# Sheet3.net
KiCad netlist of a schematic drawn in Altium Designer
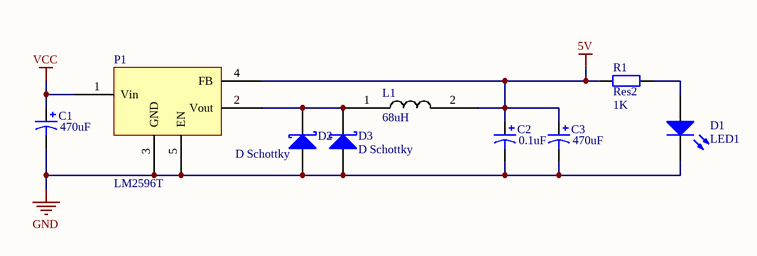
[diagram p0: Sheet3.SchDoc]

(export (version "E")
  (design (tool "Eeschema 10.0.6"))
  (components
    (comp (ref "C1")
      (value "470uF")
      (footprint "C_470uF")
      (description "Polarized Capacitor (Radial)")
      (fields (field (name "Comment") "Cap Pol1") (field (name "PUBLISHER") "Altium Limited"))
      (libsource (lib "Miscellaneous Devices") (part "Cap Pol1"))
    )
    (comp (ref "C2")
      (value "0.1uF")
      (footprint "C-pF")
      (description "Polarized Capacitor (Radial)")
      (fields (field (name "Comment") "Cap Pol1") (field (name "PUBLISHER") "Altium Limited"))
      (libsource (lib "Miscellaneous Devices") (part "Cap Pol1"))
    )
    (comp (ref "C3")
      (value "470uF")
      (footprint "C_470uF")
      (description "Polarized Capacitor (Radial)")
      (fields (field (name "Comment") "Cap Pol1") (field (name "PUBLISHER") "Altium Limited"))
      (libsource (lib "Miscellaneous Devices") (part "Cap Pol1"))
    )
    (comp (ref "D1")
      (value "LED1")
      (footprint "LED")
      (description "Typical RED GaAs LED")
      (fields (field (name "PUBLISHER") "Altium Limited"))
      (libsource (lib "Miscellaneous Devices") (part "LED1"))
    )
    (comp (ref "D2")
      (value "D Schottky")
      (footprint "Diode")
      (description "Schottky Diode")
      (fields (field (name "PUBLISHER") "Altium Limited"))
      (libsource (lib "Miscellaneous Devices") (part "D Schottky"))
    )
    (comp (ref "D3")
      (value "D Schottky")
      (footprint "Diode")
      (description "Schottky Diode")
      (fields (field (name "PUBLISHER") "Altium Limited"))
      (libsource (lib "Miscellaneous Devices") (part "D Schottky"))
    )
    (comp (ref "L1") (value "68uH") (footprint "L-") (libsource (lib "sharing_Library1") (part "L")))
    (comp (ref "P1")
      (value "LM2596T")
      (footprint "LM2596-ChaJian")
      (libsource (lib "sharing_Library1") (part "LM2596T"))
    )
    (comp (ref "R1")
      (value "Res2")
      (footprint "R")
      (description "Resistor")
      (fields (field (name "ALTIUM_VALUE") "1K") (field (name "PUBLISHER") "Altium Limited"))
      (libsource (lib "Miscellaneous Devices") (part "Res2"))
    )
  )
  (nets
    (net (code "1") (name "5V") (class "Default")
      (node (ref "C2") (pin "1") (pinfunction "1_1") (pintype "passive"))
      (node (ref "C3") (pin "1") (pinfunction "1_1") (pintype "passive"))
      (node (ref "L1") (pin "2") (pinfunction "2_2") (pintype "passive"))
      (node (ref "P1") (pin "4") (pinfunction "FB_4") (pintype "passive"))
      (node (ref "R1") (pin "2") (pinfunction "2_2") (pintype "passive"))
    )
    (net (code "2") (name "GND") (class "Default")
      (node (ref "C1") (pin "2") (pinfunction "2_2") (pintype "passive"))
      (node (ref "C2") (pin "2") (pinfunction "2_2") (pintype "passive"))
      (node (ref "C3") (pin "2") (pinfunction "2_2") (pintype "passive"))
      (node (ref "D1") (pin "2") (pinfunction "K_2") (pintype "passive"))
      (node (ref "D2") (pin "1") (pinfunction "A_1") (pintype "passive"))
      (node (ref "D3") (pin "1") (pinfunction "A_1") (pintype "passive"))
      (node (ref "P1") (pin "3") (pinfunction "GND_3") (pintype "passive"))
      (node (ref "P1") (pin "5") (pinfunction "EN_5") (pintype "passive"))
    )
    (net (code "3") (name "Net-(D1-A)") (class "Default")
      (node (ref "D1") (pin "1") (pinfunction "A_1") (pintype "passive"))
      (node (ref "R1") (pin "1") (pinfunction "1_1") (pintype "passive"))
    )
    (net (code "4") (name "Net-(D2-K)") (class "Default")
      (node (ref "D2") (pin "2") (pinfunction "K_2") (pintype "passive"))
      (node (ref "D3") (pin "2") (pinfunction "K_2") (pintype "passive"))
      (node (ref "L1") (pin "1") (pinfunction "1_1") (pintype "passive"))
      (node (ref "P1") (pin "2") (pinfunction "Vout_2") (pintype "passive"))
    )
    (net (code "5") (name "VCC") (class "Default")
      (node (ref "C1") (pin "1") (pinfunction "1_1") (pintype "passive"))
      (node (ref "P1") (pin "1") (pinfunction "Vin_1") (pintype "passive"))
    )
  )
)
